# Mote.net
KiCad netlist of a schematic drawn in EAGLE
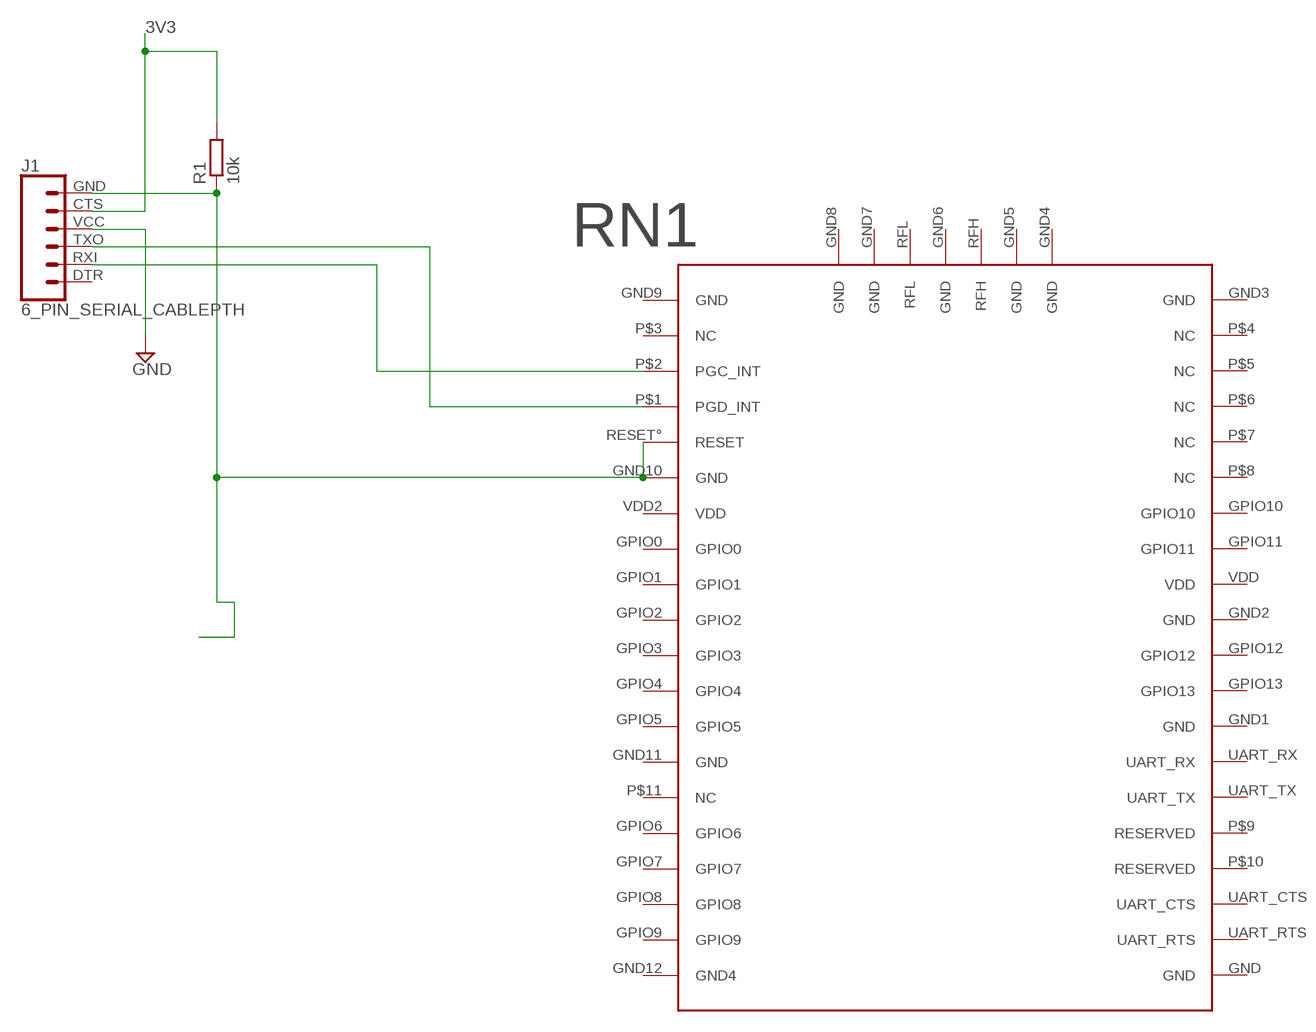
[diagram p0: schematic, sheet 1]

(export (version "E")
  (design (tool "Eeschema 10.0.6"))
  (components
    (comp (ref "J1")
      (value "6_PIN_SERIAL_CABLEPTH")
      (footprint "eagle-import:FTDI_BASIC")
      (libsource (lib "eagle-import") (part "6_PIN_SERIAL_CABLEPTH"))
    )
    (comp (ref "R1")
      (value "10k")
      (footprint "eagle-import:R0603")
      (libsource (lib "eagle-import") (part "R-EU_R0603"))
    )
    (comp (ref "RN1")
      (value "NEW_RN2483")
      (footprint "eagle-import:NEW_RN2483")
      (libsource (lib "eagle-import") (part "NEW_RN2483"))
    )
  )
  (nets
    (net (code "1") (name "/3V3") (class "Default")
      (node (ref "J1") (pin "CTS") (pinfunction "5_CTS") (pintype "passive"))
      (node (ref "R1") (pin "2") (pinfunction "2_2") (pintype "passive"))
    )
    (net (code "2") (name "GND") (class "Default")
      (node (ref "J1") (pin "VCC") (pinfunction "4_VCC") (pintype "passive"))
    )
    (net (code "3") (name "Net-(J1-2)") (class "Default")
      (node (ref "J1") (pin "RXI") (pinfunction "2_RXI") (pintype "passive"))
      (node (ref "RN1") (pin "P$2") (pinfunction "PGC_INT_P$2") (pintype "bidirectional"))
    )
    (net (code "4") (name "Net-(J1-3)") (class "Default")
      (node (ref "J1") (pin "TXO") (pinfunction "3_TXO") (pintype "passive"))
      (node (ref "RN1") (pin "P$1") (pinfunction "PGD_INT_P$1") (pintype "bidirectional"))
    )
    (net (code "5") (name "Net-(J1-6)") (class "Default")
      (node (ref "J1") (pin "GND") (pinfunction "6_GND") (pintype "passive"))
      (node (ref "R1") (pin "1") (pinfunction "1_1") (pintype "passive"))
      (node (ref "RN1") (pin "GND10") (pinfunction "GND_GND10") (pintype "bidirectional"))
      (node (ref "RN1") (pin "RESET°") (pinfunction "RESET_RESET°") (pintype "bidirectional"))
    )
    (net (code "6") (name "unconnected-(J1-1-PadDTR)") (class "Default")
      (node (ref "J1") (pin "DTR") (pinfunction "1_DTR") (pintype "passive"))
    )
    (net (code "7") (name "unconnected-(RN1-GND-PadGND1)") (class "Default")
      (node (ref "RN1") (pin "GND1") (pinfunction "GND_GND1") (pintype "bidirectional"))
    )
    (net (code "8") (name "unconnected-(RN1-GND-PadGND2)") (class "Default")
      (node (ref "RN1") (pin "GND2") (pinfunction "GND_GND2") (pintype "bidirectional"))
    )
    (net (code "9") (name "unconnected-(RN1-GND-PadGND3)") (class "Default")
      (node (ref "RN1") (pin "GND3") (pinfunction "GND_GND3") (pintype "bidirectional"))
    )
    (net (code "10") (name "unconnected-(RN1-GND-PadGND4)") (class "Default")
      (node (ref "RN1") (pin "GND4") (pinfunction "GND_GND4") (pintype "bidirectional"))
    )
    (net (code "11") (name "unconnected-(RN1-GND-PadGND5)") (class "Default")
      (node (ref "RN1") (pin "GND5") (pinfunction "GND_GND5") (pintype "bidirectional"))
    )
    (net (code "12") (name "unconnected-(RN1-GND-PadGND6)") (class "Default")
      (node (ref "RN1") (pin "GND6") (pinfunction "GND_GND6") (pintype "bidirectional"))
    )
    (net (code "13") (name "unconnected-(RN1-GND-PadGND7)") (class "Default")
      (node (ref "RN1") (pin "GND7") (pinfunction "GND_GND7") (pintype "bidirectional"))
    )
    (net (code "14") (name "unconnected-(RN1-GND-PadGND8)") (class "Default")
      (node (ref "RN1") (pin "GND8") (pinfunction "GND_GND8") (pintype "bidirectional"))
    )
    (net (code "15") (name "unconnected-(RN1-GND-PadGND9)") (class "Default")
      (node (ref "RN1") (pin "GND9") (pinfunction "GND_GND9") (pintype "bidirectional"))
    )
    (net (code "16") (name "unconnected-(RN1-GND-PadGND11)") (class "Default")
      (node (ref "RN1") (pin "GND11") (pinfunction "GND_GND11") (pintype "bidirectional"))
    )
    (net (code "17") (name "unconnected-(RN1-GND4-PadGND12)") (class "Default")
      (node (ref "RN1") (pin "GND12") (pinfunction "GND4_GND12") (pintype "bidirectional"))
    )
    (net (code "18") (name "unconnected-(RN1-NC-PadP$3)") (class "Default")
      (node (ref "RN1") (pin "P$3") (pinfunction "NC_P$3") (pintype "bidirectional"))
    )
    (net (code "19") (name "unconnected-(RN1-NC-PadP$4)") (class "Default")
      (node (ref "RN1") (pin "P$4") (pinfunction "NC_P$4") (pintype "bidirectional"))
    )
    (net (code "20") (name "unconnected-(RN1-NC-PadP$5)") (class "Default")
      (node (ref "RN1") (pin "P$5") (pinfunction "NC_P$5") (pintype "bidirectional"))
    )
    (net (code "21") (name "unconnected-(RN1-NC-PadP$6)") (class "Default")
      (node (ref "RN1") (pin "P$6") (pinfunction "NC_P$6") (pintype "bidirectional"))
    )
    (net (code "22") (name "unconnected-(RN1-NC-PadP$7)") (class "Default")
      (node (ref "RN1") (pin "P$7") (pinfunction "NC_P$7") (pintype "bidirectional"))
    )
    (net (code "23") (name "unconnected-(RN1-NC-PadP$8)") (class "Default")
      (node (ref "RN1") (pin "P$8") (pinfunction "NC_P$8") (pintype "bidirectional"))
    )
    (net (code "24") (name "unconnected-(RN1-NC-PadP$11)") (class "Default")
      (node (ref "RN1") (pin "P$11") (pinfunction "NC_P$11") (pintype "bidirectional"))
    )
    (net (code "25") (name "unconnected-(RN1-PadGND)") (class "Default")
      (node (ref "RN1") (pin "GND") (pinfunction "GND_GND") (pintype "bidirectional"))
    )
    (net (code "26") (name "unconnected-(RN1-PadGPIO0)") (class "Default")
      (node (ref "RN1") (pin "GPIO0") (pinfunction "GPIO0_GPIO0") (pintype "bidirectional"))
    )
    (net (code "27") (name "unconnected-(RN1-PadGPIO1)") (class "Default")
      (node (ref "RN1") (pin "GPIO1") (pinfunction "GPIO1_GPIO1") (pintype "bidirectional"))
    )
    (net (code "28") (name "unconnected-(RN1-PadGPIO2)") (class "Default")
      (node (ref "RN1") (pin "GPIO2") (pinfunction "GPIO2_GPIO2") (pintype "bidirectional"))
    )
    (net (code "29") (name "unconnected-(RN1-PadGPIO3)") (class "Default")
      (node (ref "RN1") (pin "GPIO3") (pinfunction "GPIO3_GPIO3") (pintype "bidirectional"))
    )
    (net (code "30") (name "unconnected-(RN1-PadGPIO4)") (class "Default")
      (node (ref "RN1") (pin "GPIO4") (pinfunction "GPIO4_GPIO4") (pintype "bidirectional"))
    )
    (net (code "31") (name "unconnected-(RN1-PadGPIO5)") (class "Default")
      (node (ref "RN1") (pin "GPIO5") (pinfunction "GPIO5_GPIO5") (pintype "bidirectional"))
    )
    (net (code "32") (name "unconnected-(RN1-PadGPIO6)") (class "Default")
      (node (ref "RN1") (pin "GPIO6") (pinfunction "GPIO6_GPIO6") (pintype "bidirectional"))
    )
    (net (code "33") (name "unconnected-(RN1-PadGPIO7)") (class "Default")
      (node (ref "RN1") (pin "GPIO7") (pinfunction "GPIO7_GPIO7") (pintype "bidirectional"))
    )
    (net (code "34") (name "unconnected-(RN1-PadGPIO8)") (class "Default")
      (node (ref "RN1") (pin "GPIO8") (pinfunction "GPIO8_GPIO8") (pintype "bidirectional"))
    )
    (net (code "35") (name "unconnected-(RN1-PadGPIO9)") (class "Default")
      (node (ref "RN1") (pin "GPIO9") (pinfunction "GPIO9_GPIO9") (pintype "bidirectional"))
    )
    (net (code "36") (name "unconnected-(RN1-PadGPIO10)") (class "Default")
      (node (ref "RN1") (pin "GPIO10") (pinfunction "GPIO10_GPIO10") (pintype "bidirectional"))
    )
    (net (code "37") (name "unconnected-(RN1-PadGPIO11)") (class "Default")
      (node (ref "RN1") (pin "GPIO11") (pinfunction "GPIO11_GPIO11") (pintype "bidirectional"))
    )
    (net (code "38") (name "unconnected-(RN1-PadGPIO12)") (class "Default")
      (node (ref "RN1") (pin "GPIO12") (pinfunction "GPIO12_GPIO12") (pintype "bidirectional"))
    )
    (net (code "39") (name "unconnected-(RN1-PadGPIO13)") (class "Default")
      (node (ref "RN1") (pin "GPIO13") (pinfunction "GPIO13_GPIO13") (pintype "bidirectional"))
    )
    (net (code "40") (name "unconnected-(RN1-PadRFH)") (class "Default")
      (node (ref "RN1") (pin "RFH") (pinfunction "RFH_RFH") (pintype "bidirectional"))
    )
    (net (code "41") (name "unconnected-(RN1-PadRFL)") (class "Default")
      (node (ref "RN1") (pin "RFL") (pinfunction "RFL_RFL") (pintype "bidirectional"))
    )
    (net (code "42") (name "unconnected-(RN1-PadUART_CTS)") (class "Default")
      (node (ref "RN1") (pin "UART_CTS") (pinfunction "UART_CTS_UART_CTS") (pintype "bidirectional"))
    )
    (net (code "43") (name "unconnected-(RN1-PadUART_RTS)") (class "Default")
      (node (ref "RN1") (pin "UART_RTS") (pinfunction "UART_RTS_UART_RTS") (pintype "bidirectional"))
    )
    (net (code "44") (name "unconnected-(RN1-PadUART_RX)") (class "Default")
      (node (ref "RN1") (pin "UART_RX") (pinfunction "UART_RX_UART_RX") (pintype "bidirectional"))
    )
    (net (code "45") (name "unconnected-(RN1-PadUART_TX)") (class "Default")
      (node (ref "RN1") (pin "UART_TX") (pinfunction "UART_TX_UART_TX") (pintype "bidirectional"))
    )
    (net (code "46") (name "unconnected-(RN1-PadVDD)") (class "Default")
      (node (ref "RN1") (pin "VDD") (pinfunction "VDD_VDD") (pintype "bidirectional"))
    )
    (net (code "47") (name "unconnected-(RN1-RESERVED-PadP$9)") (class "Default")
      (node (ref "RN1") (pin "P$9") (pinfunction "RESERVED_P$9") (pintype "bidirectional"))
    )
    (net (code "48") (name "unconnected-(RN1-RESERVED-PadP$10)") (class "Default")
      (node (ref "RN1") (pin "P$10") (pinfunction "RESERVED_P$10") (pintype "bidirectional"))
    )
    (net (code "49") (name "unconnected-(RN1-VDD-PadVDD2)") (class "Default")
      (node (ref "RN1") (pin "VDD2") (pinfunction "VDD_VDD2") (pintype "bidirectional"))
    )
  )
)
